# main.net
KiCad netlist of a schematic drawn in EAGLE
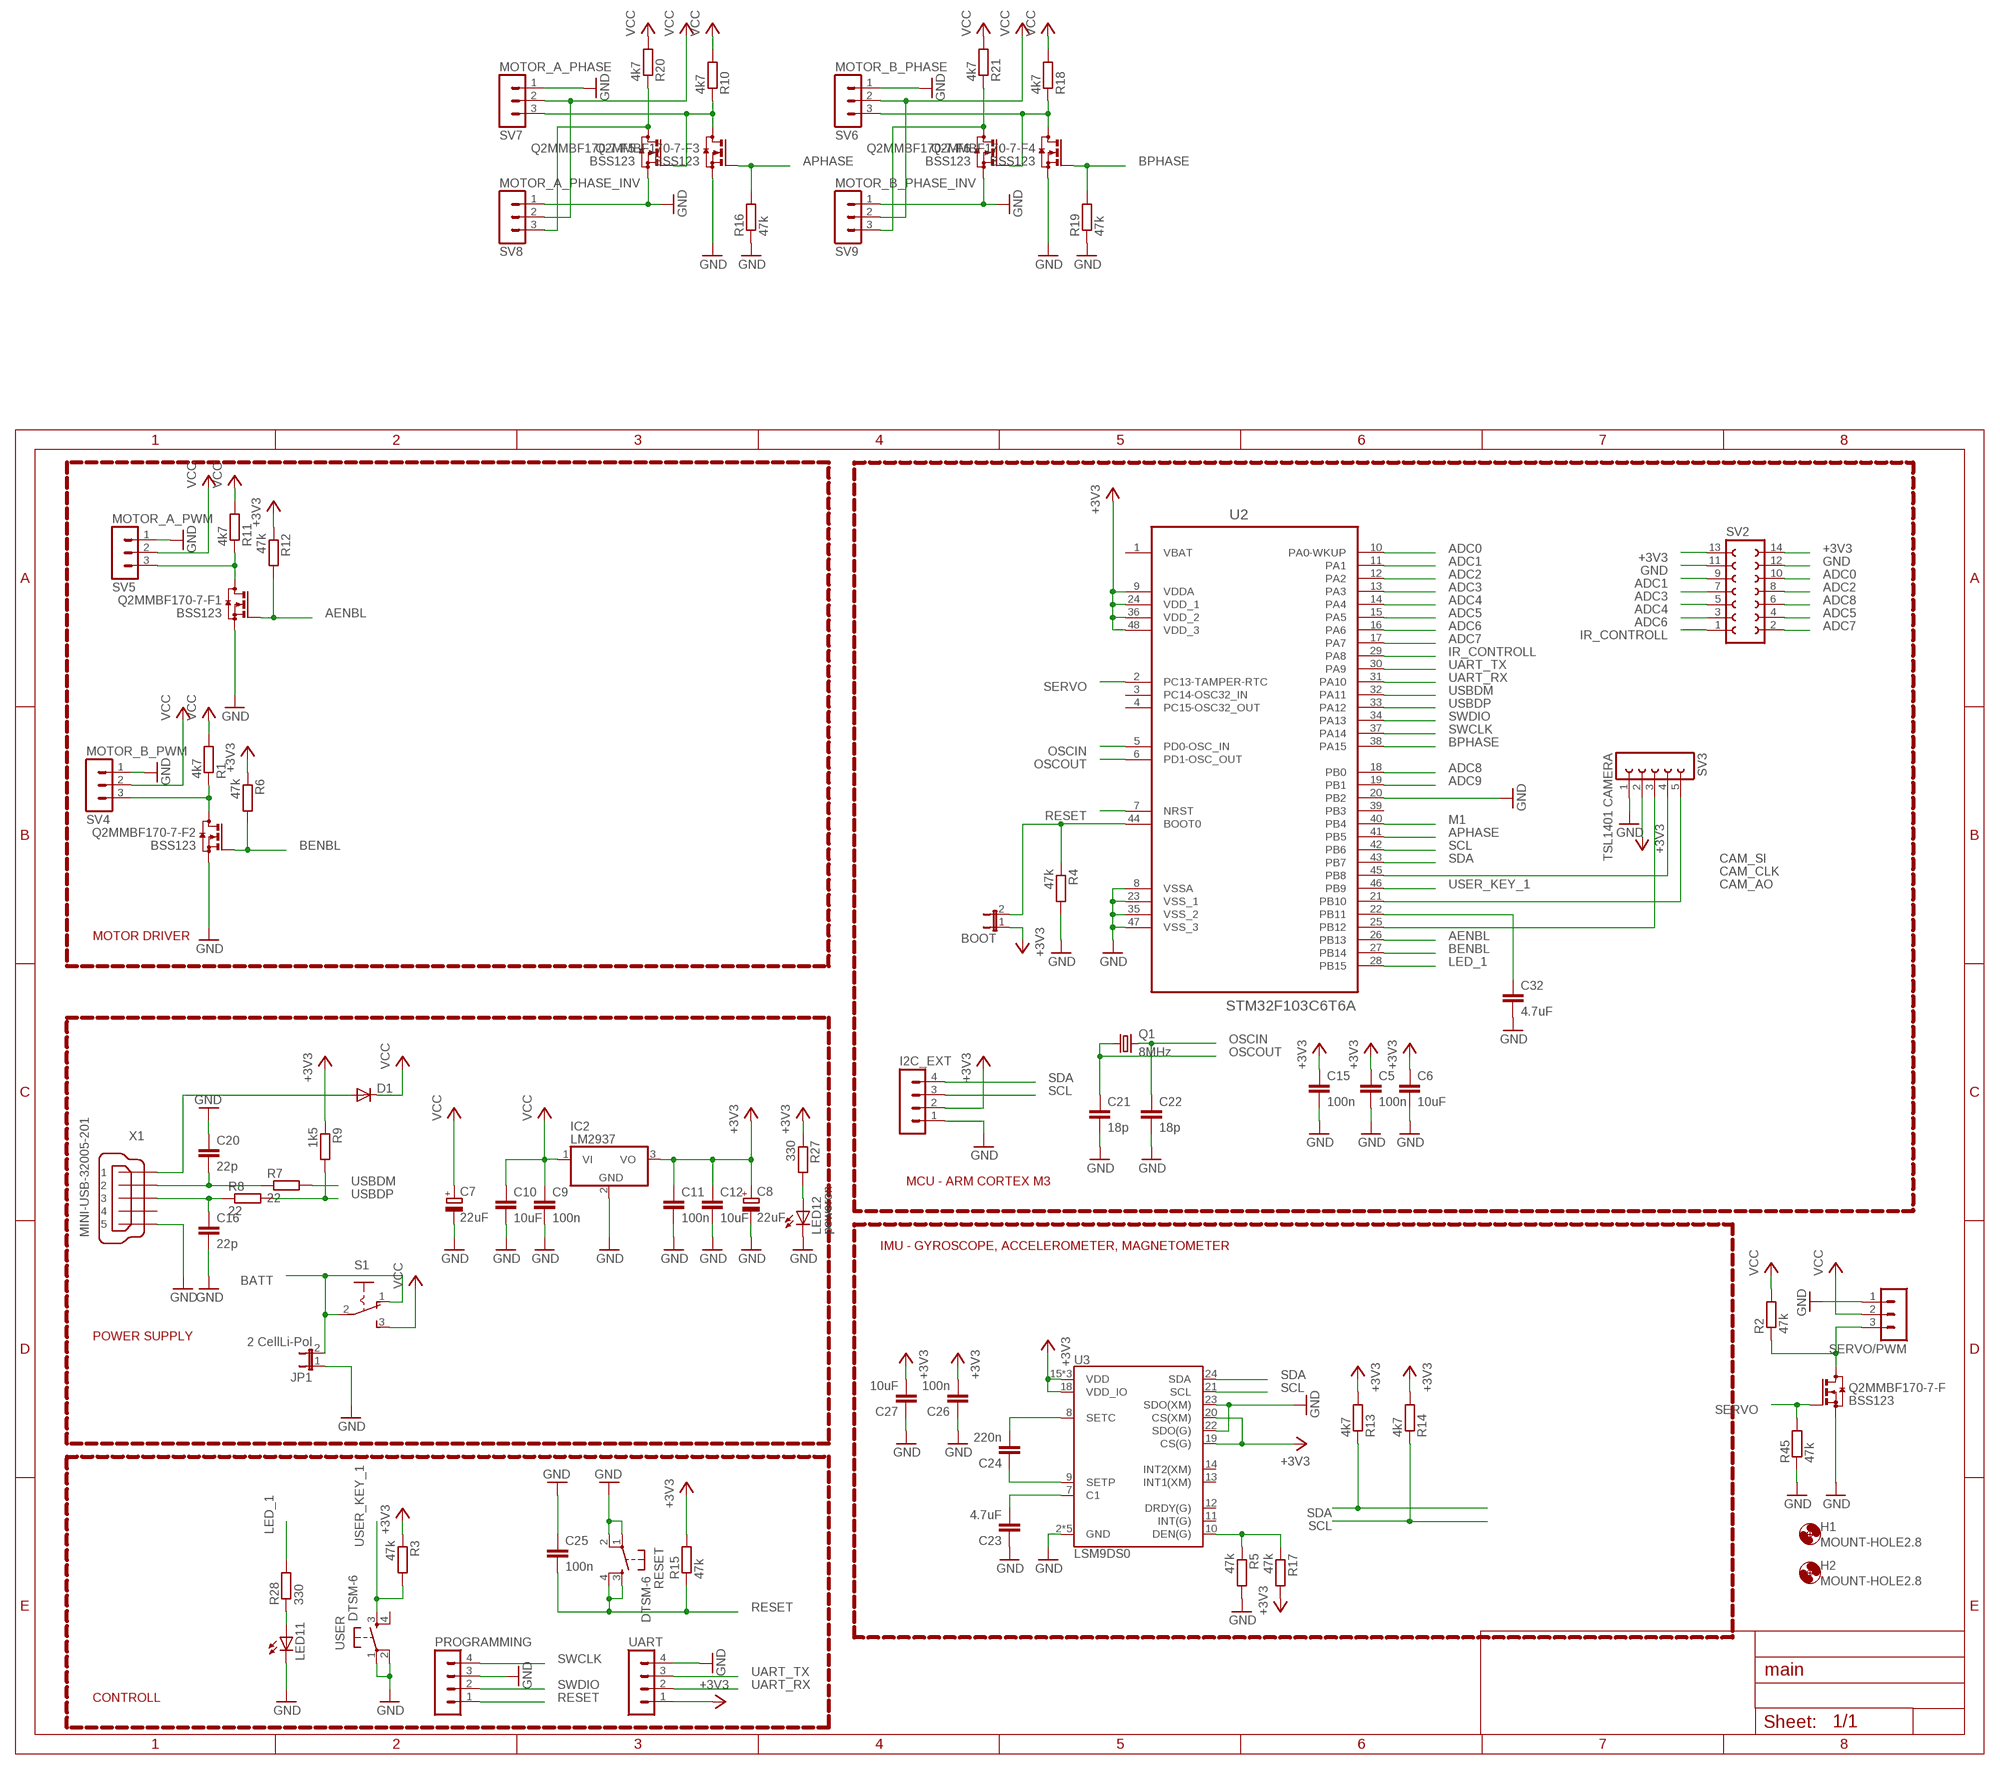
[diagram p0: schematic, sheet 1]

(export (version "E")
  (design (tool "Eeschema 10.0.6"))
  (components
    (comp (ref "BOOT")
      (value "JP1E")
      (footprint "eagle-import:JP1")
      (libsource (lib "eagle-import") (part "JP1E"))
    )
    (comp (ref "C5")
      (value "100n")
      (footprint "eagle-import:C0805")
      (libsource (lib "eagle-import") (part "C-EUC0805"))
    )
    (comp (ref "C6")
      (value "10uF")
      (footprint "eagle-import:C0805")
      (libsource (lib "eagle-import") (part "C-EUC0805"))
    )
    (comp (ref "C7")
      (value "22uF")
      (footprint "eagle-import:153CLV-0505")
      (libsource (lib "eagle-import") (part "CPOL-EU153CLV-0505"))
    )
    (comp (ref "C8")
      (value "22uF")
      (footprint "eagle-import:153CLV-0505")
      (libsource (lib "eagle-import") (part "CPOL-EU153CLV-0505"))
    )
    (comp (ref "C9")
      (value "100n")
      (footprint "eagle-import:C0805")
      (libsource (lib "eagle-import") (part "C-EUC0805"))
    )
    (comp (ref "C10")
      (value "10uF")
      (footprint "eagle-import:C0805")
      (libsource (lib "eagle-import") (part "C-EUC0805"))
    )
    (comp (ref "C11")
      (value "100n")
      (footprint "eagle-import:C0805")
      (libsource (lib "eagle-import") (part "C-EUC0805"))
    )
    (comp (ref "C12")
      (value "10uF")
      (footprint "eagle-import:C0805")
      (libsource (lib "eagle-import") (part "C-EUC0805"))
    )
    (comp (ref "C15")
      (value "100n")
      (footprint "eagle-import:C0805")
      (libsource (lib "eagle-import") (part "C-EUC0805"))
    )
    (comp (ref "C16")
      (value "22p")
      (footprint "eagle-import:C0805")
      (libsource (lib "eagle-import") (part "C-EUC0805"))
    )
    (comp (ref "C20")
      (value "22p")
      (footprint "eagle-import:C0805")
      (libsource (lib "eagle-import") (part "C-EUC0805"))
    )
    (comp (ref "C21")
      (value "18p")
      (footprint "eagle-import:C0805")
      (libsource (lib "eagle-import") (part "C-EUC0805"))
    )
    (comp (ref "C22")
      (value "18p")
      (footprint "eagle-import:C0805")
      (libsource (lib "eagle-import") (part "C-EUC0805"))
    )
    (comp (ref "C23")
      (value "4.7uF")
      (footprint "eagle-import:C0805")
      (libsource (lib "eagle-import") (part "C-EUC0805"))
    )
    (comp (ref "C24")
      (value "220n")
      (footprint "eagle-import:C0805")
      (libsource (lib "eagle-import") (part "C-EUC0805"))
    )
    (comp (ref "C25")
      (value "100n")
      (footprint "eagle-import:C0805")
      (libsource (lib "eagle-import") (part "C-EUC0805"))
    )
    (comp (ref "C26")
      (value "100n")
      (footprint "eagle-import:C0805")
      (libsource (lib "eagle-import") (part "C-EUC0805"))
    )
    (comp (ref "C27")
      (value "10uF")
      (footprint "eagle-import:C0805")
      (libsource (lib "eagle-import") (part "C-EUC0805"))
    )
    (comp (ref "C32")
      (value "4.7uF")
      (footprint "eagle-import:C0805")
      (libsource (lib "eagle-import") (part "C-EUC0805"))
    )
    (comp (ref "D1")
      (value "DIODE-SMB")
      (footprint "eagle-import:SMB")
      (libsource (lib "eagle-import") (part "DIODE-SMB"))
    )
    (comp (ref "H1")
      (value "MOUNT-HOLE2.8")
      (footprint "eagle-import:2,8")
      (libsource (lib "eagle-import") (part "MOUNT-HOLE2.8"))
    )
    (comp (ref "H2")
      (value "MOUNT-HOLE2.8")
      (footprint "eagle-import:2,8")
      (libsource (lib "eagle-import") (part "MOUNT-HOLE2.8"))
    )
    (comp (ref "I2C_EXT")
      (value "MA04-1")
      (footprint "eagle-import:MA04-1")
      (libsource (lib "eagle-import") (part "MA04-1"))
    )
    (comp (ref "IC2")
      (value "LM2937")
      (footprint "eagle-import:TO263-3")
      (libsource (lib "eagle-import") (part "LM2937"))
    )
    (comp (ref "JP1")
      (value "2 CellLi-Pol")
      (footprint "eagle-import:JP1")
      (libsource (lib "eagle-import") (part "JP1E"))
    )
    (comp (ref "LED11")
      (value "LEDCHIPLED_1206")
      (footprint "eagle-import:CHIPLED_1206")
      (libsource (lib "eagle-import") (part "LEDCHIPLED_1206"))
    )
    (comp (ref "LED12")
      (value "poweron")
      (footprint "eagle-import:CHIPLED_1206")
      (libsource (lib "eagle-import") (part "LEDCHIPLED_1206"))
    )
    (comp (ref "PROGRAMMING")
      (value "MA04-1")
      (footprint "eagle-import:MA04-1")
      (libsource (lib "eagle-import") (part "MA04-1"))
    )
    (comp (ref "Q1")
      (value "8MHz")
      (footprint "eagle-import:CTS406")
      (libsource (lib "eagle-import") (part "CRYSTALCTS406"))
    )
    (comp (ref "Q2MMBF170-7-F")
      (value "BSS123")
      (footprint "eagle-import:SOT23")
      (libsource (lib "eagle-import") (part "BSS123"))
    )
    (comp (ref "Q2MMBF170-7-F1")
      (value "BSS123")
      (footprint "eagle-import:SOT23")
      (libsource (lib "eagle-import") (part "BSS123"))
    )
    (comp (ref "Q2MMBF170-7-F2")
      (value "BSS123")
      (footprint "eagle-import:SOT23")
      (libsource (lib "eagle-import") (part "BSS123"))
    )
    (comp (ref "Q2MMBF170-7-F3")
      (value "BSS123")
      (footprint "eagle-import:SOT23")
      (libsource (lib "eagle-import") (part "BSS123"))
    )
    (comp (ref "Q2MMBF170-7-F4")
      (value "BSS123")
      (footprint "eagle-import:SOT23")
      (libsource (lib "eagle-import") (part "BSS123"))
    )
    (comp (ref "Q2MMBF170-7-F5")
      (value "BSS123")
      (footprint "eagle-import:SOT23")
      (libsource (lib "eagle-import") (part "BSS123"))
    )
    (comp (ref "Q2MMBF170-7-F6")
      (value "BSS123")
      (footprint "eagle-import:SOT23")
      (libsource (lib "eagle-import") (part "BSS123"))
    )
    (comp (ref "R1")
      (value "4k7")
      (footprint "eagle-import:M0805")
      (libsource (lib "eagle-import") (part "R-EU_M0805"))
    )
    (comp (ref "R2")
      (value "47k")
      (footprint "eagle-import:M0805")
      (libsource (lib "eagle-import") (part "R-EU_M0805"))
    )
    (comp (ref "R3")
      (value "47k")
      (footprint "eagle-import:M0805")
      (libsource (lib "eagle-import") (part "R-EU_M0805"))
    )
    (comp (ref "R4")
      (value "47k")
      (footprint "eagle-import:M0805")
      (libsource (lib "eagle-import") (part "R-EU_M0805"))
    )
    (comp (ref "R5")
      (value "47k")
      (footprint "eagle-import:M0805")
      (libsource (lib "eagle-import") (part "R-EU_M0805"))
    )
    (comp (ref "R6")
      (value "47k")
      (footprint "eagle-import:M0805")
      (libsource (lib "eagle-import") (part "R-EU_M0805"))
    )
    (comp (ref "R7")
      (value "22")
      (footprint "eagle-import:M0805")
      (libsource (lib "eagle-import") (part "R-EU_M0805"))
    )
    (comp (ref "R8")
      (value "22")
      (footprint "eagle-import:M0805")
      (libsource (lib "eagle-import") (part "R-EU_M0805"))
    )
    (comp (ref "R9")
      (value "1k5")
      (footprint "eagle-import:M0805")
      (libsource (lib "eagle-import") (part "R-EU_M0805"))
    )
    (comp (ref "R10")
      (value "4k7")
      (footprint "eagle-import:M0805")
      (libsource (lib "eagle-import") (part "R-EU_M0805"))
    )
    (comp (ref "R11")
      (value "4k7")
      (footprint "eagle-import:M0805")
      (libsource (lib "eagle-import") (part "R-EU_M0805"))
    )
    (comp (ref "R12")
      (value "47k")
      (footprint "eagle-import:M0805")
      (libsource (lib "eagle-import") (part "R-EU_M0805"))
    )
    (comp (ref "R13")
      (value "4k7")
      (footprint "eagle-import:M0805")
      (libsource (lib "eagle-import") (part "R-EU_M0805"))
    )
    (comp (ref "R14")
      (value "4k7")
      (footprint "eagle-import:M0805")
      (libsource (lib "eagle-import") (part "R-EU_M0805"))
    )
    (comp (ref "R15")
      (value "47k")
      (footprint "eagle-import:M0805")
      (libsource (lib "eagle-import") (part "R-EU_M0805"))
    )
    (comp (ref "R16")
      (value "47k")
      (footprint "eagle-import:M0805")
      (libsource (lib "eagle-import") (part "R-EU_M0805"))
    )
    (comp (ref "R17")
      (value "47k")
      (footprint "eagle-import:M0805")
      (libsource (lib "eagle-import") (part "R-EU_M0805"))
    )
    (comp (ref "R18")
      (value "4k7")
      (footprint "eagle-import:M0805")
      (libsource (lib "eagle-import") (part "R-EU_M0805"))
    )
    (comp (ref "R19")
      (value "47k")
      (footprint "eagle-import:M0805")
      (libsource (lib "eagle-import") (part "R-EU_M0805"))
    )
    (comp (ref "R20")
      (value "4k7")
      (footprint "eagle-import:M0805")
      (libsource (lib "eagle-import") (part "R-EU_M0805"))
    )
    (comp (ref "R21")
      (value "4k7")
      (footprint "eagle-import:M0805")
      (libsource (lib "eagle-import") (part "R-EU_M0805"))
    )
    (comp (ref "R27")
      (value "330")
      (footprint "eagle-import:M0805")
      (libsource (lib "eagle-import") (part "R-EU_M0805"))
    )
    (comp (ref "R28")
      (value "330")
      (footprint "eagle-import:M0805")
      (libsource (lib "eagle-import") (part "R-EU_M0805"))
    )
    (comp (ref "R45")
      (value "47k")
      (footprint "eagle-import:M0805")
      (libsource (lib "eagle-import") (part "R-EU_M0805"))
    )
    (comp (ref "RESET")
      (value "DTSM-6")
      (footprint "eagle-import:DTSM-6")
      (libsource (lib "eagle-import") (part "DTSM-6"))
    )
    (comp (ref "S1")
      (value "255SB")
      (footprint "eagle-import:255SB")
      (libsource (lib "eagle-import") (part "255SB"))
    )
    (comp (ref "SERVO/PWM")
      (value "MA03-1")
      (footprint "eagle-import:MA03-1")
      (libsource (lib "eagle-import") (part "MA03-1"))
    )
    (comp (ref "SV2")
      (value "FE07-2")
      (footprint "eagle-import:FE07-2")
      (libsource (lib "eagle-import") (part "FE07-2"))
    )
    (comp (ref "SV3")
      (value "TSL1401 CAMERA")
      (footprint "eagle-import:FE05-1")
      (libsource (lib "eagle-import") (part "FE05-1"))
    )
    (comp (ref "SV4")
      (value "MOTOR_B_PWM")
      (footprint "eagle-import:MA03-1")
      (libsource (lib "eagle-import") (part "MA03-1"))
    )
    (comp (ref "SV5")
      (value "MOTOR_A_PWM")
      (footprint "eagle-import:MA03-1")
      (libsource (lib "eagle-import") (part "MA03-1"))
    )
    (comp (ref "SV6")
      (value "MOTOR_B_PHASE")
      (footprint "eagle-import:MA03-1")
      (libsource (lib "eagle-import") (part "MA03-1"))
    )
    (comp (ref "SV7")
      (value "MOTOR_A_PHASE")
      (footprint "eagle-import:MA03-1")
      (libsource (lib "eagle-import") (part "MA03-1"))
    )
    (comp (ref "SV8")
      (value "MOTOR_A_PHASE_INV")
      (footprint "eagle-import:MA03-1")
      (libsource (lib "eagle-import") (part "MA03-1"))
    )
    (comp (ref "SV9")
      (value "MOTOR_B_PHASE_INV")
      (footprint "eagle-import:MA03-1")
      (libsource (lib "eagle-import") (part "MA03-1"))
    )
    (comp (ref "U2")
      (value "STM32F103C6T6A")
      (footprint "eagle-import:QFP50P900X900X160-48N")
      (libsource (lib "eagle-import") (part "STM32F103C6T6A"))
    )
    (comp (ref "U3")
      (value "LSM9DS0")
      (footprint "eagle-import:LGA-24")
      (libsource (lib "eagle-import") (part "LSM9DS0"))
    )
    (comp (ref "UART")
      (value "MA04-1")
      (footprint "eagle-import:MA04-1")
      (libsource (lib "eagle-import") (part "MA04-1"))
    )
    (comp (ref "USER")
      (value "DTSM-6")
      (footprint "eagle-import:DTSM-6")
      (libsource (lib "eagle-import") (part "DTSM-6"))
    )
    (comp (ref "X1")
      (value "MINI-USB-32005-201")
      (footprint "eagle-import:32005-201")
      (libsource (lib "eagle-import") (part "MINI-USB-32005-201"))
    )
  )
  (nets
    (net (code "1") (name "+3V3") (class "Default")
      (node (ref "BOOT") (pin "1") (pinfunction "1_1") (pintype "passive"))
      (node (ref "C11") (pin "1") (pinfunction "1_1") (pintype "passive"))
      (node (ref "C12") (pin "1") (pinfunction "1_1") (pintype "passive"))
      (node (ref "C15") (pin "1") (pinfunction "1_1") (pintype "passive"))
      (node (ref "C26") (pin "2") (pinfunction "2_2") (pintype "passive"))
      (node (ref "C27") (pin "2") (pinfunction "2_2") (pintype "passive"))
      (node (ref "C5") (pin "1") (pinfunction "1_1") (pintype "passive"))
      (node (ref "C6") (pin "1") (pinfunction "1_1") (pintype "passive"))
      (node (ref "C8") (pin "+") (pinfunction "+_+") (pintype "passive"))
      (node (ref "I2C_EXT") (pin "2") (pinfunction "2_2") (pintype "passive"))
      (node (ref "IC2") (pin "3") (pinfunction "VO_3") (pintype "passive"))
      (node (ref "R12") (pin "1") (pinfunction "1_1") (pintype "passive"))
      (node (ref "R13") (pin "2") (pinfunction "2_2") (pintype "passive"))
      (node (ref "R14") (pin "2") (pinfunction "2_2") (pintype "passive"))
      (node (ref "R15") (pin "2") (pinfunction "2_2") (pintype "passive"))
      (node (ref "R17") (pin "2") (pinfunction "2_2") (pintype "passive"))
      (node (ref "R27") (pin "1") (pinfunction "1_1") (pintype "passive"))
      (node (ref "R3") (pin "1") (pinfunction "1_1") (pintype "passive"))
      (node (ref "R6") (pin "1") (pinfunction "1_1") (pintype "passive"))
      (node (ref "R9") (pin "1") (pinfunction "1_1") (pintype "passive"))
      (node (ref "SV2") (pin "13") (pinfunction "13_13") (pintype "passive"))
      (node (ref "SV2") (pin "14") (pinfunction "14_14") (pintype "passive"))
      (node (ref "SV3") (pin "2") (pinfunction "2_2") (pintype "passive"))
      (node (ref "U2") (pin "24") (pinfunction "VDD_1_24") (pintype "power_in"))
      (node (ref "U2") (pin "36") (pinfunction "VDD_2_36") (pintype "power_in"))
      (node (ref "U2") (pin "48") (pinfunction "VDD_3_48") (pintype "power_in"))
      (node (ref "U2") (pin "9") (pinfunction "VDDA_9") (pintype "power_in"))
      (node (ref "U3") (pin "15") (pinfunction "VDD_15") (pintype "bidirectional"))
      (node (ref "U3") (pin "16") (pinfunction "VDD_16") (pintype "bidirectional"))
      (node (ref "U3") (pin "17") (pinfunction "VDD_17") (pintype "bidirectional"))
      (node (ref "U3") (pin "18") (pinfunction "VDD_IO_18") (pintype "bidirectional"))
      (node (ref "U3") (pin "19") (pinfunction "CS(G)_19") (pintype "bidirectional"))
      (node (ref "U3") (pin "20") (pinfunction "CS(XM)_20") (pintype "bidirectional"))
      (node (ref "UART") (pin "1") (pinfunction "1_1") (pintype "passive"))
    )
    (net (code "2") (name "/ADC0") (class "Default")
      (node (ref "SV2") (pin "10") (pinfunction "10_10") (pintype "passive"))
      (node (ref "U2") (pin "10") (pinfunction "PA0-WKUP_10") (pintype "bidirectional"))
    )
    (net (code "3") (name "/ADC1") (class "Default")
      (node (ref "SV2") (pin "9") (pinfunction "9_9") (pintype "passive"))
      (node (ref "U2") (pin "11") (pinfunction "PA1_11") (pintype "bidirectional"))
    )
    (net (code "4") (name "/ADC2") (class "Default")
      (node (ref "SV2") (pin "8") (pinfunction "8_8") (pintype "passive"))
      (node (ref "U2") (pin "12") (pinfunction "PA2_12") (pintype "bidirectional"))
    )
    (net (code "5") (name "/ADC3") (class "Default")
      (node (ref "SV2") (pin "7") (pinfunction "7_7") (pintype "passive"))
      (node (ref "U2") (pin "13") (pinfunction "PA3_13") (pintype "bidirectional"))
    )
    (net (code "6") (name "/ADC4") (class "Default")
      (node (ref "SV2") (pin "5") (pinfunction "5_5") (pintype "passive"))
      (node (ref "U2") (pin "14") (pinfunction "PA4_14") (pintype "bidirectional"))
    )
    (net (code "7") (name "/ADC5") (class "Default")
      (node (ref "SV2") (pin "4") (pinfunction "4_4") (pintype "passive"))
      (node (ref "U2") (pin "15") (pinfunction "PA5_15") (pintype "bidirectional"))
    )
    (net (code "8") (name "/ADC6") (class "Default")
      (node (ref "SV2") (pin "3") (pinfunction "3_3") (pintype "passive"))
      (node (ref "U2") (pin "16") (pinfunction "PA6_16") (pintype "bidirectional"))
    )
    (net (code "9") (name "/ADC7") (class "Default")
      (node (ref "SV2") (pin "2") (pinfunction "2_2") (pintype "passive"))
      (node (ref "U2") (pin "17") (pinfunction "PA7_17") (pintype "bidirectional"))
    )
    (net (code "10") (name "/ADC8") (class "Default")
      (node (ref "SV2") (pin "6") (pinfunction "6_6") (pintype "passive"))
      (node (ref "U2") (pin "18") (pinfunction "PB0_18") (pintype "bidirectional"))
    )
    (net (code "11") (name "/ADC9") (class "Default")
      (node (ref "U2") (pin "19") (pinfunction "PB1_19") (pintype "bidirectional"))
    )
    (net (code "12") (name "/AENBL") (class "Default")
      (node (ref "Q2MMBF170-7-F1") (pin "1") (pinfunction "G_1") (pintype "passive"))
      (node (ref "R12") (pin "2") (pinfunction "2_2") (pintype "passive"))
      (node (ref "U2") (pin "26") (pinfunction "PB13_26") (pintype "bidirectional"))
    )
    (net (code "13") (name "/APHASE") (class "Default")
      (node (ref "Q2MMBF170-7-F3") (pin "1") (pinfunction "G_1") (pintype "passive"))
      (node (ref "R16") (pin "2") (pinfunction "2_2") (pintype "passive"))
      (node (ref "U2") (pin "41") (pinfunction "PB5_41") (pintype "bidirectional"))
    )
    (net (code "14") (name "/BATT") (class "Default")
      (node (ref "JP1") (pin "2") (pinfunction "2_2") (pintype "passive"))
      (node (ref "S1") (pin "1") (pinfunction "O_1") (pintype "passive"))
      (node (ref "S1") (pin "2") (pinfunction "P_2") (pintype "passive"))
    )
    (net (code "15") (name "/BENBL") (class "Default")
      (node (ref "Q2MMBF170-7-F2") (pin "1") (pinfunction "G_1") (pintype "passive"))
      (node (ref "R6") (pin "2") (pinfunction "2_2") (pintype "passive"))
      (node (ref "U2") (pin "27") (pinfunction "PB14_27") (pintype "bidirectional"))
    )
    (net (code "16") (name "/BPHASE") (class "Default")
      (node (ref "Q2MMBF170-7-F4") (pin "1") (pinfunction "G_1") (pintype "passive"))
      (node (ref "R19") (pin "2") (pinfunction "2_2") (pintype "passive"))
      (node (ref "U2") (pin "38") (pinfunction "PA15_38") (pintype "bidirectional"))
    )
    (net (code "17") (name "/CAM_AO") (class "Default")
      (node (ref "SV3") (pin "3") (pinfunction "3_3") (pintype "passive"))
      (node (ref "U2") (pin "25") (pinfunction "PB12_25") (pintype "bidirectional"))
    )
    (net (code "18") (name "/CAM_CLK") (class "Default")
      (node (ref "SV3") (pin "4") (pinfunction "4_4") (pintype "passive"))
      (node (ref "U2") (pin "45") (pinfunction "PB8_45") (pintype "bidirectional"))
    )
    (net (code "19") (name "/CAM_SI") (class "Default")
      (node (ref "SV3") (pin "5") (pinfunction "5_5") (pintype "passive"))
      (node (ref "U2") (pin "21") (pinfunction "PB10_21") (pintype "bidirectional"))
    )
    (net (code "20") (name "/IR_CONTROLL") (class "Default")
      (node (ref "SV2") (pin "1") (pinfunction "1_1") (pintype "passive"))
      (node (ref "U2") (pin "29") (pinfunction "PA8_29") (pintype "bidirectional"))
    )
    (net (code "21") (name "/LED_1") (class "Default")
      (node (ref "R28") (pin "2") (pinfunction "2_2") (pintype "passive"))
      (node (ref "U2") (pin "28") (pinfunction "PB15_28") (pintype "bidirectional"))
    )
    (net (code "22") (name "/M1") (class "Default")
      (node (ref "U2") (pin "40") (pinfunction "PB4_40") (pintype "bidirectional"))
    )
    (net (code "23") (name "/OSCIN") (class "Default")
      (node (ref "C22") (pin "1") (pinfunction "1_1") (pintype "passive"))
      (node (ref "Q1") (pin "3") (pinfunction "2_3") (pintype "passive"))
      (node (ref "U2") (pin "5") (pinfunction "PD0-OSC_IN_5") (pintype "bidirectional"))
    )
    (net (code "24") (name "/OSCOUT") (class "Default")
      (node (ref "C21") (pin "1") (pinfunction "1_1") (pintype "passive"))
      (node (ref "Q1") (pin "1") (pinfunction "1_1") (pintype "passive"))
      (node (ref "U2") (pin "6") (pinfunction "PD1-OSC_OUT_6") (pintype "bidirectional"))
    )
    (net (code "25") (name "/RESET") (class "Default")
      (node (ref "C25") (pin "2") (pinfunction "2_2") (pintype "passive"))
      (node (ref "PROGRAMMING") (pin "1") (pinfunction "1_1") (pintype "passive"))
      (node (ref "R15") (pin "1") (pinfunction "1_1") (pintype "passive"))
      (node (ref "RESET") (pin "3") (pinfunction "3_3") (pintype "passive"))
      (node (ref "RESET") (pin "4") (pinfunction "4_4") (pintype "passive"))
      (node (ref "U2") (pin "7") (pinfunction "NRST_7") (pintype "bidirectional"))
    )
    (net (code "26") (name "/SCL") (class "Default")
      (node (ref "I2C_EXT") (pin "3") (pinfunction "3_3") (pintype "passive"))
      (node (ref "R14") (pin "1") (pinfunction "1_1") (pintype "passive"))
      (node (ref "U2") (pin "42") (pinfunction "PB6_42") (pintype "bidirectional"))
      (node (ref "U3") (pin "21") (pinfunction "SCL_21") (pintype "bidirectional"))
    )
    (net (code "27") (name "/SDA") (class "Default")
      (node (ref "I2C_EXT") (pin "4") (pinfunction "4_4") (pintype "passive"))
      (node (ref "R13") (pin "1") (pinfunction "1_1") (pintype "passive"))
      (node (ref "U2") (pin "43") (pinfunction "PB7_43") (pintype "bidirectional"))
      (node (ref "U3") (pin "24") (pinfunction "SDA_24") (pintype "bidirectional"))
    )
    (net (code "28") (name "/SERVO") (class "Default")
      (node (ref "Q2MMBF170-7-F") (pin "1") (pinfunction "G_1") (pintype "passive"))
      (node (ref "R45") (pin "2") (pinfunction "2_2") (pintype "passive"))
      (node (ref "U2") (pin "2") (pinfunction "PC13-TAMPER-RTC_2") (pintype "bidirectional"))
    )
    (net (code "29") (name "/SWCLK") (class "Default")
      (node (ref "PROGRAMMING") (pin "4") (pinfunction "4_4") (pintype "passive"))
      (node (ref "U2") (pin "37") (pinfunction "PA14_37") (pintype "bidirectional"))
    )
    (net (code "30") (name "/SWDIO") (class "Default")
      (node (ref "PROGRAMMING") (pin "2") (pinfunction "2_2") (pintype "passive"))
      (node (ref "U2") (pin "34") (pinfunction "PA13_34") (pintype "bidirectional"))
    )
    (net (code "31") (name "/UART_RX") (class "Default")
      (node (ref "U2") (pin "31") (pinfunction "PA10_31") (pintype "bidirectional"))
      (node (ref "UART") (pin "2") (pinfunction "2_2") (pintype "passive"))
    )
    (net (code "32") (name "/UART_TX") (class "Default")
      (node (ref "U2") (pin "30") (pinfunction "PA9_30") (pintype "bidirectional"))
      (node (ref "UART") (pin "3") (pinfunction "3_3") (pintype "passive"))
    )
    (net (code "33") (name "/USBDM") (class "Default")
      (node (ref "R7") (pin "2") (pinfunction "2_2") (pintype "passive"))
      (node (ref "U2") (pin "32") (pinfunction "PA11_32") (pintype "bidirectional"))
    )
    (net (code "34") (name "/USBDP") (class "Default")
      (node (ref "R8") (pin "2") (pinfunction "2_2") (pintype "passive"))
      (node (ref "R9") (pin "2") (pinfunction "2_2") (pintype "passive"))
      (node (ref "U2") (pin "33") (pinfunction "PA12_33") (pintype "bidirectional"))
    )
    (net (code "35") (name "/USER_KEY_1") (class "Default")
      (node (ref "R3") (pin "2") (pinfunction "2_2") (pintype "passive"))
      (node (ref "U2") (pin "46") (pinfunction "PB9_46") (pintype "bidirectional"))
      (node (ref "USER") (pin "3") (pinfunction "3_3") (pintype "passive"))
    )
    (net (code "36") (name "/VBAT") (class "Default")
      (node (ref "U2") (pin "1") (pinfunction "VBAT_1") (pintype "power_in"))
    )
    (net (code "37") (name "GND") (class "Default")
      (node (ref "C10") (pin "2") (pinfunction "2_2") (pintype "passive"))
      (node (ref "C11") (pin "2") (pinfunction "2_2") (pintype "passive"))
      (node (ref "C12") (pin "2") (pinfunction "2_2") (pintype "passive"))
      (node (ref "C15") (pin "2") (pinfunction "2_2") (pintype "passive"))
      (node (ref "C16") (pin "2") (pinfunction "2_2") (pintype "passive"))
      (node (ref "C20") (pin "1") (pinfunction "1_1") (pintype "passive"))
      (node (ref "C21") (pin "2") (pinfunction "2_2") (pintype "passive"))
      (node (ref "C22") (pin "2") (pinfunction "2_2") (pintype "passive"))
      (node (ref "C23") (pin "1") (pinfunction "1_1") (pintype "passive"))
      (node (ref "C25") (pin "1") (pinfunction "1_1") (pintype "passive"))
      (node (ref "C26") (pin "1") (pinfunction "1_1") (pintype "passive"))
      (node (ref "C27") (pin "1") (pinfunction "1_1") (pintype "passive"))
      (node (ref "C32") (pin "2") (pinfunction "2_2") (pintype "passive"))
      (node (ref "C5") (pin "2") (pinfunction "2_2") (pintype "passive"))
      (node (ref "C6") (pin "2") (pinfunction "2_2") (pintype "passive"))
      (node (ref "C7") (pin "-") (pinfunction "-_-") (pintype "passive"))
      (node (ref "C8") (pin "-") (pinfunction "-_-") (pintype "passive"))
      (node (ref "C9") (pin "2") (pinfunction "2_2") (pintype "passive"))
      (node (ref "I2C_EXT") (pin "1") (pinfunction "1_1") (pintype "passive"))
      (node (ref "IC2") (pin "2") (pinfunction "GND_2") (pintype "passive"))
      (node (ref "JP1") (pin "1") (pinfunction "1_1") (pintype "passive"))
      (node (ref "LED11") (pin "C") (pinfunction "C_C") (pintype "passive"))
      (node (ref "LED12") (pin "C") (pinfunction "C_C") (pintype "passive"))
      (node (ref "PROGRAMMING") (pin "3") (pinfunction "3_3") (pintype "passive"))
      (node (ref "Q2MMBF170-7-F") (pin "2") (pinfunction "S_2") (pintype "passive"))
      (node (ref "Q2MMBF170-7-F1") (pin "2") (pinfunction "S_2") (pintype "passive"))
      (node (ref "Q2MMBF170-7-F2") (pin "2") (pinfunction "S_2") (pintype "passive"))
      (node (ref "Q2MMBF170-7-F3") (pin "2") (pinfunction "S_2") (pintype "passive"))
      (node (ref "Q2MMBF170-7-F4") (pin "2") (pinfunction "S_2") (pintype "passive"))
      (node (ref "Q2MMBF170-7-F5") (pin "2") (pinfunction "S_2") (pintype "passive"))
      (node (ref "Q2MMBF170-7-F6") (pin "2") (pinfunction "S_2") (pintype "passive"))
      (node (ref "R16") (pin "1") (pinfunction "1_1") (pintype "passive"))
      (node (ref "R19") (pin "1") (pinfunction "1_1") (pintype "passive"))
      (node (ref "R4") (pin "2") (pinfunction "2_2") (pintype "passive"))
      (node (ref "R45") (pin "1") (pinfunction "1_1") (pintype "passive"))
      (node (ref "R5") (pin "2") (pinfunction "2_2") (pintype "passive"))
      (node (ref "RESET") (pin "1") (pinfunction "1_1") (pintype "passive"))
      (node (ref "RESET") (pin "2") (pinfunction "2_2") (pintype "passive"))
      (node (ref "SERVO/PWM") (pin "1") (pinfunction "1_1") (pintype "passive"))
      (node (ref "SV2") (pin "11") (pinfunction "11_11") (pintype "passive"))
      (node (ref "SV2") (pin "12") (pinfunction "12_12") (pintype "passive"))
      (node (ref "SV3") (pin "1") (pinfunction "1_1") (pintype "passive"))
      (node (ref "SV4") (pin "1") (pinfunction "1_1") (pintype "passive"))
      (node (ref "SV5") (pin "1") (pinfunction "1_1") (pintype "passive"))
      (node (ref "SV6") (pin "1") (pinfunction "1_1") (pintype "passive"))
      (node (ref "SV7") (pin "1") (pinfunction "1_1") (pintype "passive"))
      (node (ref "SV8") (pin "1") (pinfunction "1_1") (pintype "passive"))
      (node (ref "SV9") (pin "1") (pinfunction "1_1") (pintype "passive"))
      (node (ref "U2") (pin "20") (pinfunction "PB2_20") (pintype "bidirectional"))
      (node (ref "U2") (pin "23") (pinfunction "VSS_1_23") (pintype "passive"))
      (node (ref "U2") (pin "35") (pinfunction "VSS_2_35") (pintype "passive"))
      (node (ref "U2") (pin "47") (pinfunction "VSS_3_47") (pintype "passive"))
      (node (ref "U2") (pin "8") (pinfunction "VSSA_8") (pintype "passive"))
      (node (ref "U3") (pin "2") (pinfunction "GND_2") (pintype "bidirectional"))
      (node (ref "U3") (pin "22") (pinfunction "SDO(G)_22") (pintype "bidirectional"))
      (node (ref "U3") (pin "23") (pinfunction "SDO(XM)_23") (pintype "bidirectional"))
      (node (ref "U3") (pin "3") (pinfunction "GND_3") (pintype "bidirectional"))
      (node (ref "U3") (pin "4") (pinfunction "GND_4") (pintype "bidirectional"))
      (node (ref "U3") (pin "5") (pinfunction "GND_5") (pintype "bidirectional"))
      (node (ref "U3") (pin "6") (pinfunction "GND_6") (pintype "bidirectional"))
      (node (ref "UART") (pin "4") (pinfunction "4_4") (pintype "passive"))
      (node (ref "USER") (pin "1") (pinfunction "1_1") (pintype "passive"))
      (node (ref "USER") (pin "2") (pinfunction "2_2") (pintype "passive"))
      (node (ref "X1") (pin "5") (pinfunction "5_5") (pintype "passive"))
    )
    (net (code "38") (name "Net-(C16-Pad1)") (class "Default")
      (node (ref "C16") (pin "1") (pinfunction "1_1") (pintype "passive"))
      (node (ref "R8") (pin "1") (pinfunction "1_1") (pintype "passive"))
      (node (ref "X1") (pin "3") (pinfunction "3_3") (pintype "passive"))
    )
    (net (code "39") (name "Net-(C20-Pad2)") (class "Default")
      (node (ref "C20") (pin "2") (pinfunction "2_2") (pintype "passive"))
      (node (ref "R7") (pin "1") (pinfunction "1_1") (pintype "passive"))
      (node (ref "X1") (pin "2") (pinfunction "2_2") (pintype "passive"))
    )
    (net (code "40") (name "Net-(D1-PadA)") (class "Default")
      (node (ref "D1") (pin "A") (pinfunction "A_A") (pintype "passive"))
      (node (ref "X1") (pin "1") (pinfunction "1_1") (pintype "passive"))
    )
    (net (code "41") (name "Net-(LED11-PadA)") (class "Default")
      (node (ref "LED11") (pin "A") (pinfunction "A_A") (pintype "passive"))
      (node (ref "R28") (pin "1") (pinfunction "1_1") (pintype "passive"))
    )
    (net (code "42") (name "Net-(LED12-PadA)") (class "Default")
      (node (ref "LED12") (pin "A") (pinfunction "A_A") (pintype "passive"))
      (node (ref "R27") (pin "2") (pinfunction "2_2") (pintype "passive"))
    )
    (net (code "43") (name "Net-(Q2MMBF170-7-F-D)") (class "Default")
      (node (ref "Q2MMBF170-7-F") (pin "3") (pinfunction "D_3") (pintype "passive"))
      (node (ref "R2") (pin "1") (pinfunction "1_1") (pintype "passive"))
      (node (ref "SERVO/PWM") (pin "3") (pinfunction "3_3") (pintype "passive"))
    )
    (net (code "44") (name "Net-(Q2MMBF170-7-F1-D)") (class "Default")
      (node (ref "Q2MMBF170-7-F1") (pin "3") (pinfunction "D_3") (pintype "passive"))
      (node (ref "R11") (pin "1") (pinfunction "1_1") (pintype "passive"))
      (node (ref "SV5") (pin "3") (pinfunction "3_3") (pintype "passive"))
    )
    (net (code "45") (name "Net-(Q2MMBF170-7-F2-D)") (class "Default")
      (node (ref "Q2MMBF170-7-F2") (pin "3") (pinfunction "D_3") (pintype "passive"))
      (node (ref "R1") (pin "1") (pinfunction "1_1") (pintype "passive"))
      (node (ref "SV4") (pin "3") (pinfunction "3_3") (pintype "passive"))
    )
    (net (code "46") (name "Net-(Q2MMBF170-7-F3-D)") (class "Default")
      (node (ref "Q2MMBF170-7-F3") (pin "3") (pinfunction "D_3") (pintype "passive"))
      (node (ref "Q2MMBF170-7-F5") (pin "1") (pinfunction "G_1") (pintype "passive"))
      (node (ref "R10") (pin "1") (pinfunction "1_1") (pintype "passive"))
      (node (ref "SV7") (pin "3") (pinfunction "3_3") (pintype "passive"))
    )
    (net (code "47") (name "Net-(Q2MMBF170-7-F4-D)") (class "Default")
      (node (ref "Q2MMBF170-7-F4") (pin "3") (pinfunction "D_3") (pintype "passive"))
      (node (ref "Q2MMBF170-7-F6") (pin "1") (pinfunction "G_1") (pintype "passive"))
      (node (ref "R18") (pin "1") (pinfunction "1_1") (pintype "passive"))
      (node (ref "SV6") (pin "3") (pinfunction "3_3") (pintype "passive"))
    )
    (net (code "48") (name "Net-(Q2MMBF170-7-F5-D)") (class "Default")
      (node (ref "Q2MMBF170-7-F5") (pin "3") (pinfunction "D_3") (pintype "passive"))
      (node (ref "R20") (pin "1") (pinfunction "1_1") (pintype "passive"))
      (node (ref "SV8") (pin "3") (pinfunction "3_3") (pintype "passive"))
    )
    (net (code "49") (name "Net-(Q2MMBF170-7-F6-D)") (class "Default")
      (node (ref "Q2MMBF170-7-F6") (pin "3") (pinfunction "D_3") (pintype "passive"))
      (node (ref "R21") (pin "1") (pinfunction "1_1") (pintype "passive"))
      (node (ref "SV9") (pin "3") (pinfunction "3_3") (pintype "passive"))
    )
    (net (code "50") (name "Net-(U2-BOOT0)") (class "Default")
      (node (ref "BOOT") (pin "2") (pinfunction "2_2") (pintype "passive"))
      (node (ref "R4") (pin "1") (pinfunction "1_1") (pintype "passive"))
      (node (ref "U2") (pin "44") (pinfunction "BOOT0_44") (pintype "input"))
    )
    (net (code "51") (name "Net-(U2-PB11)") (class "Default")
      (node (ref "C32") (pin "1") (pinfunction "1_1") (pintype "passive"))
      (node (ref "U2") (pin "22") (pinfunction "PB11_22") (pintype "bidirectional"))
    )
    (net (code "52") (name "Net-(U3-C1)") (class "Default")
      (node (ref "C23") (pin "2") (pinfunction "2_2") (pintype "passive"))
      (node (ref "U3") (pin "7") (pinfunction "C1_7") (pintype "bidirectional"))
    )
    (net (code "53") (name "Net-(U3-DEN(G))") (class "Default")
      (node (ref "R17") (pin "1") (pinfunction "1_1") (pintype "passive"))
      (node (ref "R5") (pin "1") (pinfunction "1_1") (pintype "passive"))
      (node (ref "U3") (pin "10") (pinfunction "DEN(G)_10") (pintype "bidirectional"))
    )
    (net (code "54") (name "Net-(U3-SETC)") (class "Default")
      (node (ref "C24") (pin "2") (pinfunction "2_2") (pintype "passive"))
      (node (ref "U3") (pin "8") (pinfunction "SETC_8") (pintype "bidirectional"))
    )
    (net (code "55") (name "Net-(U3-SETP)") (class "Default")
      (node (ref "C24") (pin "1") (pinfunction "1_1") (pintype "passive"))
      (node (ref "U3") (pin "9") (pinfunction "SETP_9") (pintype "bidirectional"))
    )
    (net (code "56") (name "VCC") (class "Default")
      (node (ref "C10") (pin "1") (pinfunction "1_1") (pintype "passive"))
      (node (ref "C7") (pin "+") (pinfunction "+_+") (pintype "passive"))
      (node (ref "C9") (pin "1") (pinfunction "1_1") (pintype "passive"))
      (node (ref "D1") (pin "C") (pinfunction "C_C") (pintype "passive"))
      (node (ref "IC2") (pin "1") (pinfunction "VI_1") (pintype "input"))
      (node (ref "R1") (pin "2") (pinfunction "2_2") (pintype "passive"))
      (node (ref "R10") (pin "2") (pinfunction "2_2") (pintype "passive"))
      (node (ref "R11") (pin "2") (pinfunction "2_2") (pintype "passive"))
      (node (ref "R18") (pin "2") (pinfunction "2_2") (pintype "passive"))
      (node (ref "R2") (pin "2") (pinfunction "2_2") (pintype "passive"))
      (node (ref "R20") (pin "2") (pinfunction "2_2") (pintype "passive"))
      (node (ref "R21") (pin "2") (pinfunction "2_2") (pintype "passive"))
      (node (ref "S1") (pin "3") (pinfunction "S_3") (pintype "passive"))
      (node (ref "SERVO/PWM") (pin "2") (pinfunction "2_2") (pintype "passive"))
      (node (ref "SV4") (pin "2") (pinfunction "2_2") (pintype "passive"))
      (node (ref "SV5") (pin "2") (pinfunction "2_2") (pintype "passive"))
      (node (ref "SV6") (pin "2") (pinfunction "2_2") (pintype "passive"))
      (node (ref "SV7") (pin "2") (pinfunction "2_2") (pintype "passive"))
      (node (ref "SV8") (pin "2") (pinfunction "2_2") (pintype "passive"))
      (node (ref "SV9") (pin "2") (pinfunction "2_2") (pintype "passive"))
    )
    (net (code "57") (name "unconnected-(U2-PB3-Pad39)") (class "Default")
      (node (ref "U2") (pin "39") (pinfunction "PB3_39") (pintype "bidirectional"))
    )
    (net (code "58") (name "unconnected-(U2-PC14-OSC32_IN-Pad3)") (class "Default")
      (node (ref "U2") (pin "3") (pinfunction "PC14-OSC32_IN_3") (pintype "bidirectional"))
    )
    (net (code "59") (name "unconnected-(U2-PC15-OSC32_OUT-Pad4)") (class "Default")
      (node (ref "U2") (pin "4") (pinfunction "PC15-OSC32_OUT_4") (pintype "bidirectional"))
    )
    (net (code "60") (name "unconnected-(U3-DRDY(G)-Pad12)") (class "Default")
      (node (ref "U3") (pin "12") (pinfunction "DRDY(G)_12") (pintype "bidirectional"))
    )
    (net (code "61") (name "unconnected-(U3-INT(G)-Pad11)") (class "Default")
      (node (ref "U3") (pin "11") (pinfunction "INT(G)_11") (pintype "bidirectional"))
    )
    (net (code "62") (name "unconnected-(U3-INT1(XM)-Pad13)") (class "Default")
      (node (ref "U3") (pin "13") (pinfunction "INT1(XM)_13") (pintype "bidirectional"))
    )
    (net (code "63") (name "unconnected-(U3-INT2(XM)-Pad14)") (class "Default")
      (node (ref "U3") (pin "14") (pinfunction "INT2(XM)_14") (pintype "bidirectional"))
    )
    (net (code "64") (name "unconnected-(USER-Pad4)") (class "Default")
      (node (ref "USER") (pin "4") (pinfunction "4_4") (pintype "passive"))
    )
    (net (code "65") (name "unconnected-(X1-Pad4)") (class "Default")
      (node (ref "X1") (pin "4") (pinfunction "4_4") (pintype "passive"))
    )
  )
)
